# FM375_LQFP64_SOCKET.net
KiCad netlist of a schematic drawn in Altium Designer
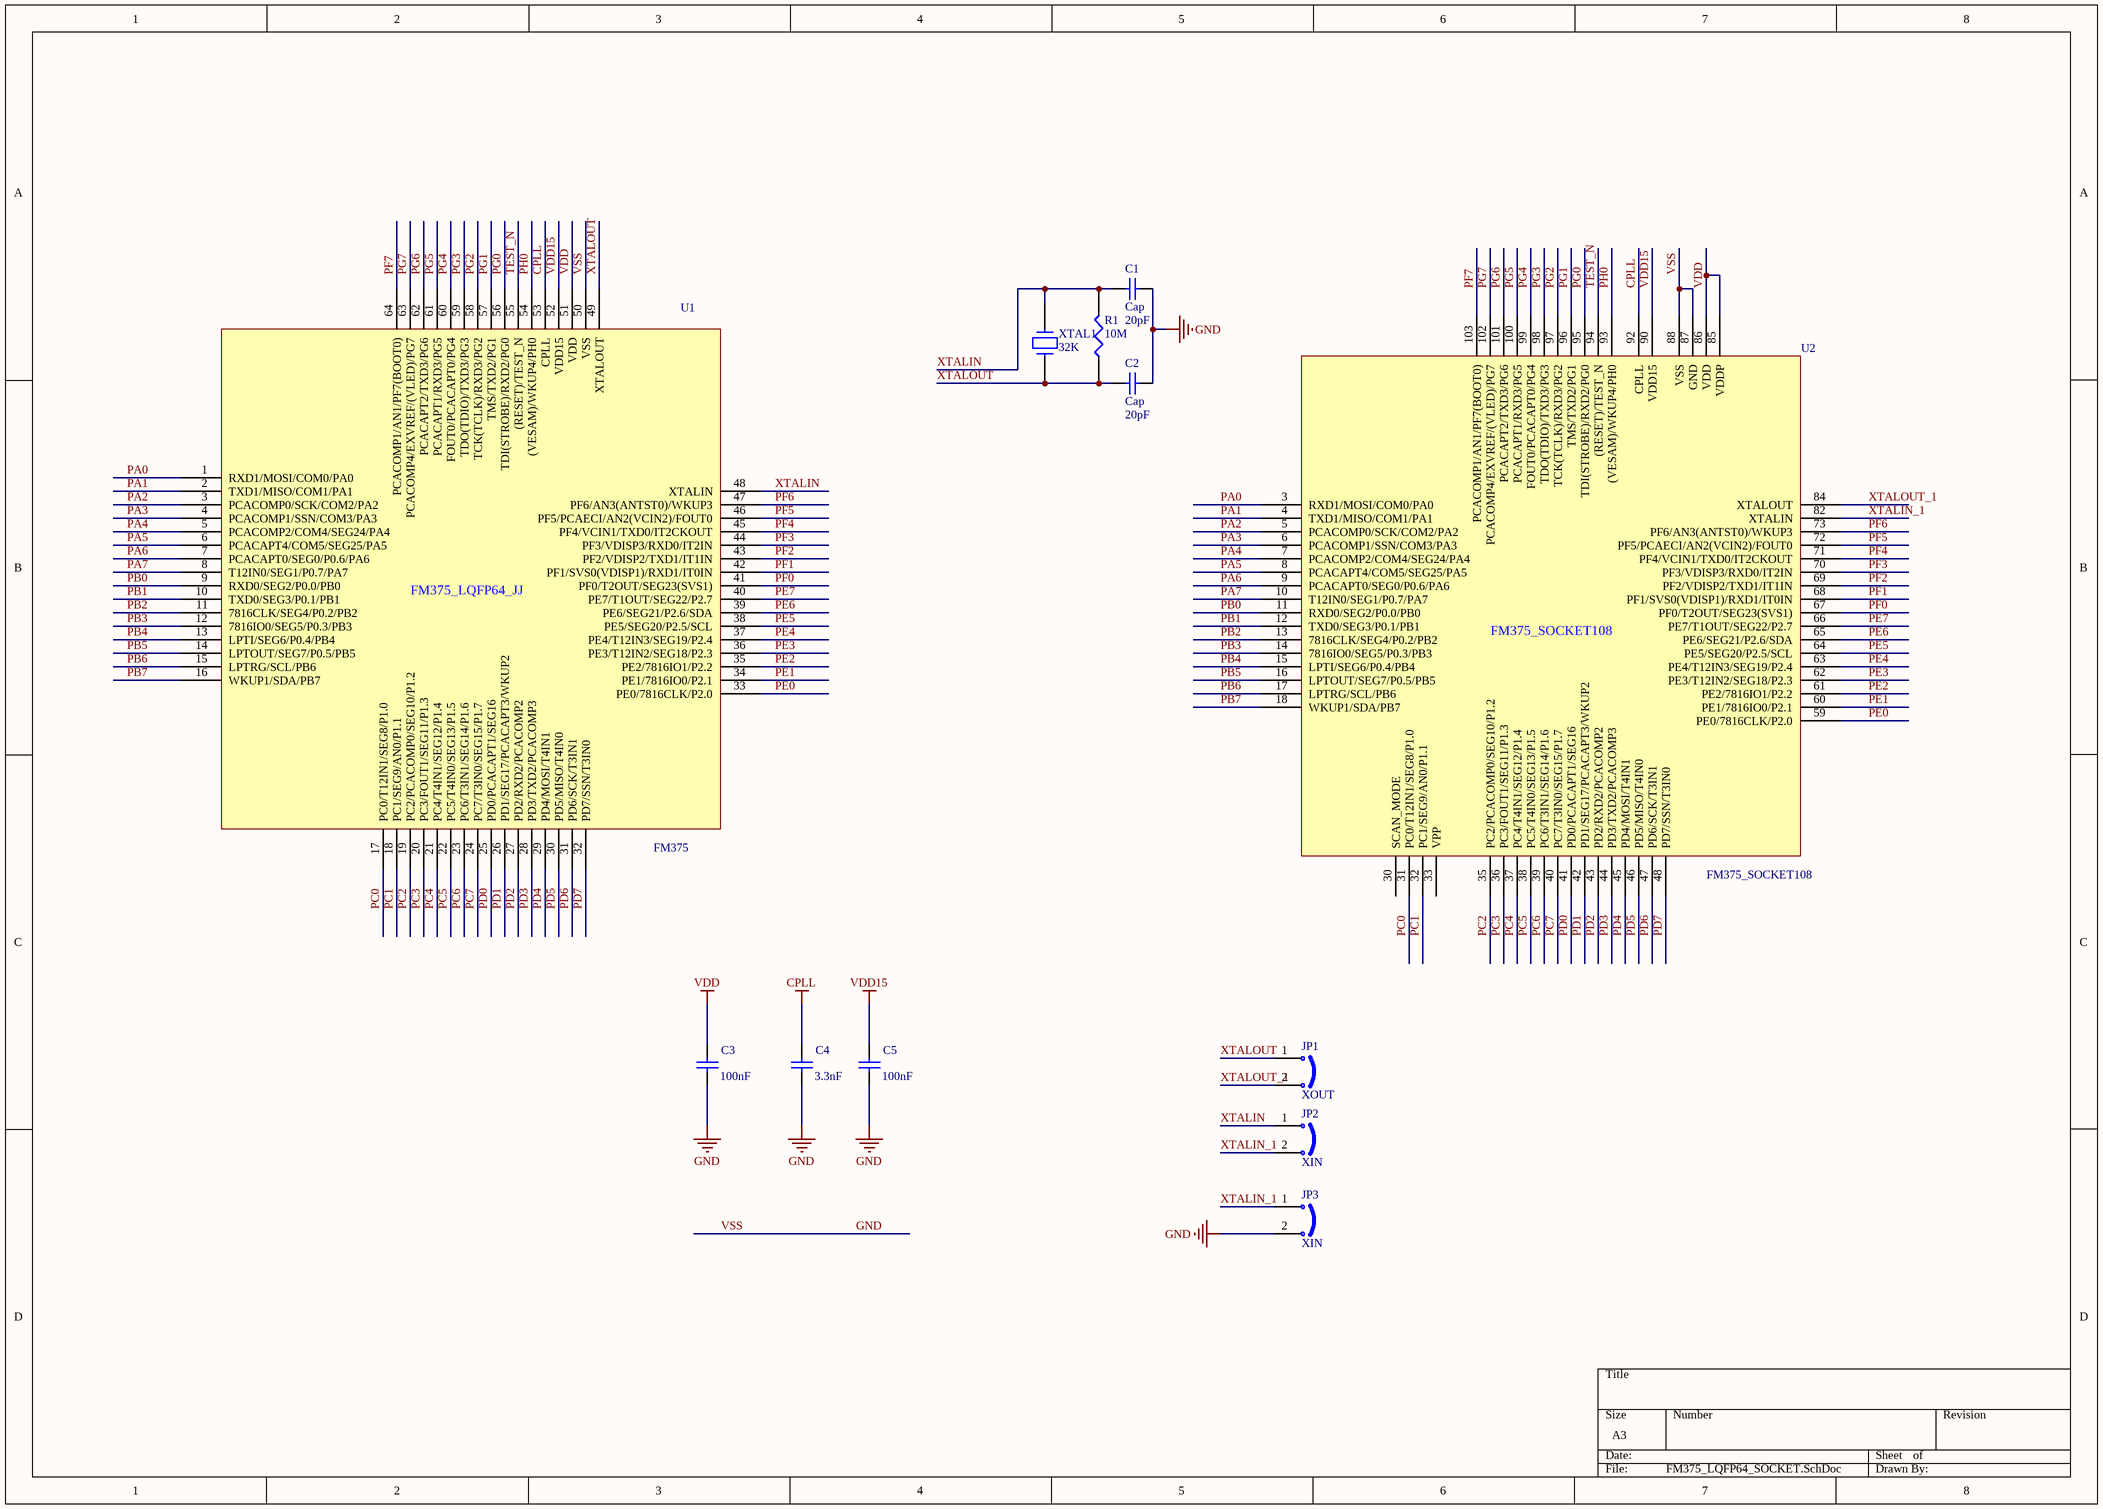
[diagram p0: FM375_LQFP64_SOCKET.SchDoc]

(export (version "E")
  (design (tool "Eeschema 10.0.6"))
  (components
    (comp (ref "C1")
      (value "Cap")
      (footprint "0805")
      (description "Capacitor")
      (fields (field (name "ALTIUM_VALUE") "20pF") (field (name "PUBLISHER") "Altium Limited"))
      (libsource (lib "Miscellaneous Devices") (part "Cap"))
    )
    (comp (ref "C2")
      (value "Cap")
      (footprint "0805")
      (description "Capacitor")
      (fields (field (name "ALTIUM_VALUE") "20pF") (field (name "PUBLISHER") "Altium Limited"))
      (libsource (lib "Miscellaneous Devices") (part "Cap"))
    )
    (comp (ref "C3")
      (value "100nF")
      (footprint "0805")
      (description "Capacitor")
      (fields (field (name "PUBLISHER") "Altium Limited"))
      (libsource (lib "Miscellaneous Devices") (part "Cap"))
    )
    (comp (ref "C4")
      (value "3.3nF")
      (footprint "0805")
      (description "Capacitor")
      (fields (field (name "PUBLISHER") "Altium Limited"))
      (libsource (lib "Miscellaneous Devices") (part "Cap"))
    )
    (comp (ref "C5")
      (value "100nF")
      (footprint "0805")
      (description "Capacitor")
      (fields (field (name "PUBLISHER") "Altium Limited"))
      (libsource (lib "Miscellaneous Devices") (part "Cap"))
    )
    (comp (ref "JP1")
      (value "XOUT")
      (footprint "0603_SHORT")
      (description "Jumper")
      (libsource (lib "FM301_TEST") (part "JUMPER"))
    )
    (comp (ref "JP2")
      (value "XIN")
      (footprint "0603_SHORT")
      (description "Jumper")
      (libsource (lib "FM301_TEST") (part "JUMPER"))
    )
    (comp (ref "JP3")
      (value "XIN")
      (footprint "FM318_SOCKET:0603_SHORT")
      (description "Jumper")
      (libsource (lib "FM301_TEST") (part "JUMPER"))
    )
    (comp (ref "R1") (value "10M") (footprint "0805") (libsource (lib "FM301_TEST") (part "RES1")))
    (comp (ref "U1")
      (value "FM375")
      (footprint "QFP64_10*10_JJ")
      (libsource (lib "FM375_LQFP64_SOCKET") (part "LQFP64-JJ"))
    )
    (comp (ref "U2")
      (value "FM375_SOCKET108")
      (footprint "SOCKET108_LARGE")
      (libsource (lib "FM375_SOCKET") (part "FM375_SOCKET108"))
    )
    (comp (ref "XTAL1")
      (value "32K")
      (footprint "XTAL-RB32K_2")
      (description "Crystal")
      (libsource (lib "FM301_TEST") (part "CRYSTAL"))
    )
  )
  (nets
    (net (code "1") (name "/PA0") (class "Default")
      (node (ref "U1") (pin "1") (pinfunction "RXD1/MOSI/COM0/PA0_1") (pintype "passive"))
      (node (ref "U2") (pin "3") (pinfunction "RXD1/MOSI/COM0/PA0_3") (pintype "passive"))
    )
    (net (code "2") (name "/PA1") (class "Default")
      (node (ref "U1") (pin "2") (pinfunction "TXD1/MISO/COM1/PA1_2") (pintype "passive"))
      (node (ref "U2") (pin "4") (pinfunction "TXD1/MISO/COM1/PA1_4") (pintype "passive"))
    )
    (net (code "3") (name "/PA2") (class "Default")
      (node (ref "U1") (pin "3") (pinfunction "PCACOMP0/SCK/COM2/PA2_3") (pintype "passive"))
      (node (ref "U2") (pin "5") (pinfunction "PCACOMP0/SCK/COM2/PA2_5") (pintype "passive"))
    )
    (net (code "4") (name "/PA3") (class "Default")
      (node (ref "U1") (pin "4") (pinfunction "PCACOMP1/SSN/COM3/PA3_4") (pintype "passive"))
      (node (ref "U2") (pin "6") (pinfunction "PCACOMP1/SSN/COM3/PA3_6") (pintype "passive"))
    )
    (net (code "5") (name "/PA4") (class "Default")
      (node (ref "U1") (pin "5") (pinfunction "PCACOMP2/COM4/SEG24/PA4_5") (pintype "passive"))
      (node (ref "U2") (pin "7") (pinfunction "PCACOMP2/COM4/SEG24/PA4_7") (pintype "passive"))
    )
    (net (code "6") (name "/PA5") (class "Default")
      (node (ref "U1") (pin "6") (pinfunction "PCACAPT4/COM5/SEG25/PA5_6") (pintype "passive"))
      (node (ref "U2") (pin "8") (pinfunction "PCACAPT4/COM5/SEG25/PA5_8") (pintype "passive"))
    )
    (net (code "7") (name "/PA6") (class "Default")
      (node (ref "U1") (pin "7") (pinfunction "PCACAPT0/SEG0/P0.6/PA6_7") (pintype "passive"))
      (node (ref "U2") (pin "9") (pinfunction "PCACAPT0/SEG0/P0.6/PA6_9") (pintype "passive"))
    )
    (net (code "8") (name "/PA7") (class "Default")
      (node (ref "U1") (pin "8") (pinfunction "T12IN0/SEG1/P0.7/PA7_8") (pintype "passive"))
      (node (ref "U2") (pin "10") (pinfunction "T12IN0/SEG1/P0.7/PA7_10") (pintype "passive"))
    )
    (net (code "9") (name "/PB0") (class "Default")
      (node (ref "U1") (pin "9") (pinfunction "RXD0/SEG2/P0.0/PB0_9") (pintype "passive"))
      (node (ref "U2") (pin "11") (pinfunction "RXD0/SEG2/P0.0/PB0_11") (pintype "passive"))
    )
    (net (code "10") (name "/PB1") (class "Default")
      (node (ref "U1") (pin "10") (pinfunction "TXD0/SEG3/P0.1/PB1_10") (pintype "passive"))
      (node (ref "U2") (pin "12") (pinfunction "TXD0/SEG3/P0.1/PB1_12") (pintype "passive"))
    )
    (net (code "11") (name "/PB2") (class "Default")
      (node (ref "U1") (pin "11") (pinfunction "7816CLK/SEG4/P0.2/PB2_11") (pintype "passive"))
      (node (ref "U2") (pin "13") (pinfunction "7816CLK/SEG4/P0.2/PB2_13") (pintype "passive"))
    )
    (net (code "12") (name "/PB3") (class "Default")
      (node (ref "U1") (pin "12") (pinfunction "7816IO0/SEG5/P0.3/PB3_12") (pintype "passive"))
      (node (ref "U2") (pin "14") (pinfunction "7816IO0/SEG5/P0.3/PB3_14") (pintype "passive"))
    )
    (net (code "13") (name "/PB4") (class "Default")
      (node (ref "U1") (pin "13") (pinfunction "LPTI/SEG6/P0.4/PB4_13") (pintype "passive"))
      (node (ref "U2") (pin "15") (pinfunction "LPTI/SEG6/P0.4/PB4_15") (pintype "passive"))
    )
    (net (code "14") (name "/PB5") (class "Default")
      (node (ref "U1") (pin "14") (pinfunction "LPTOUT/SEG7/P0.5/PB5_14") (pintype "passive"))
      (node (ref "U2") (pin "16") (pinfunction "LPTOUT/SEG7/P0.5/PB5_16") (pintype "passive"))
    )
    (net (code "15") (name "/PB6") (class "Default")
      (node (ref "U1") (pin "15") (pinfunction "LPTRG/SCL/PB6_15") (pintype "passive"))
      (node (ref "U2") (pin "17") (pinfunction "LPTRG/SCL/PB6_17") (pintype "passive"))
    )
    (net (code "16") (name "/PB7") (class "Default")
      (node (ref "U1") (pin "16") (pinfunction "WKUP1/SDA/PB7_16") (pintype "passive"))
      (node (ref "U2") (pin "18") (pinfunction "WKUP1/SDA/PB7_18") (pintype "passive"))
    )
    (net (code "17") (name "/PC0") (class "Default")
      (node (ref "U1") (pin "17") (pinfunction "PC0/T12IN1/SEG8/P1.0_17") (pintype "passive"))
      (node (ref "U2") (pin "31") (pinfunction "PC0/T12IN1/SEG8/P1.0_31") (pintype "passive"))
    )
    (net (code "18") (name "/PC1") (class "Default")
      (node (ref "U1") (pin "18") (pinfunction "PC1/SEG9/AN0/P1.1_18") (pintype "passive"))
      (node (ref "U2") (pin "32") (pinfunction "PC1/SEG9/AN0/P1.1_32") (pintype "passive"))
    )
    (net (code "19") (name "/PC2") (class "Default")
      (node (ref "U1") (pin "19") (pinfunction "PC2/PCACOMP0/SEG10/P1.2_19") (pintype "passive"))
      (node (ref "U2") (pin "35") (pinfunction "PC2/PCACOMP0/SEG10/P1.2_35") (pintype "passive"))
    )
    (net (code "20") (name "/PC3") (class "Default")
      (node (ref "U1") (pin "20") (pinfunction "PC3/FOUT1/SEG11/P1.3_20") (pintype "passive"))
      (node (ref "U2") (pin "36") (pinfunction "PC3/FOUT1/SEG11/P1.3_36") (pintype "passive"))
    )
    (net (code "21") (name "/PC4") (class "Default")
      (node (ref "U1") (pin "21") (pinfunction "PC4/T4IN1/SEG12/P1.4_21") (pintype "passive"))
      (node (ref "U2") (pin "37") (pinfunction "PC4/T4IN1/SEG12/P1.4_37") (pintype "passive"))
    )
    (net (code "22") (name "/PC5") (class "Default")
      (node (ref "U1") (pin "22") (pinfunction "PC5/T4IN0/SEG13/P1.5_22") (pintype "passive"))
      (node (ref "U2") (pin "38") (pinfunction "PC5/T4IN0/SEG13/P1.5_38") (pintype "passive"))
    )
    (net (code "23") (name "/PC6") (class "Default")
      (node (ref "U1") (pin "23") (pinfunction "PC6/T3IN1/SEG14/P1.6_23") (pintype "passive"))
      (node (ref "U2") (pin "39") (pinfunction "PC6/T3IN1/SEG14/P1.6_39") (pintype "passive"))
    )
    (net (code "24") (name "/PC7") (class "Default")
      (node (ref "U1") (pin "24") (pinfunction "PC7/T3IN0/SEG15/P1.7_24") (pintype "passive"))
      (node (ref "U2") (pin "40") (pinfunction "PC7/T3IN0/SEG15/P1.7_40") (pintype "passive"))
    )
    (net (code "25") (name "/PD0") (class "Default")
      (node (ref "U1") (pin "25") (pinfunction "PD0/PCACAPT1/SEG16_25") (pintype "passive"))
      (node (ref "U2") (pin "41") (pinfunction "PD0/PCACAPT1/SEG16_41") (pintype "passive"))
    )
    (net (code "26") (name "/PD1") (class "Default")
      (node (ref "U1") (pin "26") (pinfunction "PD1/SEG17/PCACAPT3/WKUP2_26") (pintype "passive"))
      (node (ref "U2") (pin "42") (pinfunction "PD1/SEG17/PCACAPT3/WKUP2_42") (pintype "passive"))
    )
    (net (code "27") (name "/PD2") (class "Default")
      (node (ref "U1") (pin "27") (pinfunction "PD2/RXD2/PCACOMP2_27") (pintype "passive"))
      (node (ref "U2") (pin "43") (pinfunction "PD2/RXD2/PCACOMP2_43") (pintype "passive"))
    )
    (net (code "28") (name "/PD3") (class "Default")
      (node (ref "U1") (pin "28") (pinfunction "PD3/TXD2/PCACOMP3_28") (pintype "passive"))
      (node (ref "U2") (pin "44") (pinfunction "PD3/TXD2/PCACOMP3_44") (pintype "passive"))
    )
    (net (code "29") (name "/PD4") (class "Default")
      (node (ref "U1") (pin "29") (pinfunction "PD4/MOSI/T4IN1_29") (pintype "passive"))
      (node (ref "U2") (pin "45") (pinfunction "PD4/MOSI/T4IN1_45") (pintype "passive"))
    )
    (net (code "30") (name "/PD5") (class "Default")
      (node (ref "U1") (pin "30") (pinfunction "PD5/MISO/T4IN0_30") (pintype "passive"))
      (node (ref "U2") (pin "46") (pinfunction "PD5/MISO/T4IN0_46") (pintype "passive"))
    )
    (net (code "31") (name "/PD6") (class "Default")
      (node (ref "U1") (pin "31") (pinfunction "PD6/SCK/T3IN1_31") (pintype "passive"))
      (node (ref "U2") (pin "47") (pinfunction "PD6/SCK/T3IN1_47") (pintype "passive"))
    )
    (net (code "32") (name "/PD7") (class "Default")
      (node (ref "U1") (pin "32") (pinfunction "PD7/SSN/T3IN0_32") (pintype "passive"))
      (node (ref "U2") (pin "48") (pinfunction "PD7/SSN/T3IN0_48") (pintype "passive"))
    )
    (net (code "33") (name "/PE0") (class "Default")
      (node (ref "U1") (pin "33") (pinfunction "PE0/7816CLK/P2.0_33") (pintype "passive"))
      (node (ref "U2") (pin "59") (pinfunction "PE0/7816CLK/P2.0_59") (pintype "passive"))
    )
    (net (code "34") (name "/PE1") (class "Default")
      (node (ref "U1") (pin "34") (pinfunction "PE1/7816IO0/P2.1_34") (pintype "passive"))
      (node (ref "U2") (pin "60") (pinfunction "PE1/7816IO0/P2.1_60") (pintype "passive"))
    )
    (net (code "35") (name "/PE2") (class "Default")
      (node (ref "U1") (pin "35") (pinfunction "PE2/7816IO1/P2.2_35") (pintype "passive"))
      (node (ref "U2") (pin "61") (pinfunction "PE2/7816IO1/P2.2_61") (pintype "passive"))
    )
    (net (code "36") (name "/PE3") (class "Default")
      (node (ref "U1") (pin "36") (pinfunction "PE3/T12IN2/SEG18/P2.3_36") (pintype "passive"))
      (node (ref "U2") (pin "62") (pinfunction "PE3/T12IN2/SEG18/P2.3_62") (pintype "passive"))
    )
    (net (code "37") (name "/PE4") (class "Default")
      (node (ref "U1") (pin "37") (pinfunction "PE4/T12IN3/SEG19/P2.4_37") (pintype "passive"))
      (node (ref "U2") (pin "63") (pinfunction "PE4/T12IN3/SEG19/P2.4_63") (pintype "passive"))
    )
    (net (code "38") (name "/PE5") (class "Default")
      (node (ref "U1") (pin "38") (pinfunction "PE5/SEG20/P2.5/SCL_38") (pintype "passive"))
      (node (ref "U2") (pin "64") (pinfunction "PE5/SEG20/P2.5/SCL_64") (pintype "passive"))
    )
    (net (code "39") (name "/PE6") (class "Default")
      (node (ref "U1") (pin "39") (pinfunction "PE6/SEG21/P2.6/SDA_39") (pintype "passive"))
      (node (ref "U2") (pin "65") (pinfunction "PE6/SEG21/P2.6/SDA_65") (pintype "passive"))
    )
    (net (code "40") (name "/PE7") (class "Default")
      (node (ref "U1") (pin "40") (pinfunction "PE7/T1OUT/SEG22/P2.7_40") (pintype "passive"))
      (node (ref "U2") (pin "66") (pinfunction "PE7/T1OUT/SEG22/P2.7_66") (pintype "passive"))
    )
    (net (code "41") (name "/PF0") (class "Default")
      (node (ref "U1") (pin "41") (pinfunction "PF0/T2OUT/SEG23(SVS1)_41") (pintype "passive"))
      (node (ref "U2") (pin "67") (pinfunction "PF0/T2OUT/SEG23(SVS1)_67") (pintype "passive"))
    )
    (net (code "42") (name "/PF1") (class "Default")
      (node (ref "U1") (pin "42") (pinfunction "PF1/SVS0(VDISP1)/RXD1/IT0IN_42") (pintype "passive"))
      (node (ref "U2") (pin "68") (pinfunction "PF1/SVS0(VDISP1)/RXD1/IT0IN_68") (pintype "passive"))
    )
    (net (code "43") (name "/PF2") (class "Default")
      (node (ref "U1") (pin "43") (pinfunction "PF2/VDISP2/TXD1/IT1IN_43") (pintype "passive"))
      (node (ref "U2") (pin "69") (pinfunction "PF2/VDISP2/TXD1/IT1IN_69") (pintype "passive"))
    )
    (net (code "44") (name "/PF3") (class "Default")
      (node (ref "U1") (pin "44") (pinfunction "PF3/VDISP3/RXD0/IT2IN_44") (pintype "passive"))
      (node (ref "U2") (pin "70") (pinfunction "PF3/VDISP3/RXD0/IT2IN_70") (pintype "passive"))
    )
    (net (code "45") (name "/PF4") (class "Default")
      (node (ref "U1") (pin "45") (pinfunction "PF4/VCIN1/TXD0/IT2CKOUT_45") (pintype "passive"))
      (node (ref "U2") (pin "71") (pinfunction "PF4/VCIN1/TXD0/IT2CKOUT_71") (pintype "passive"))
    )
    (net (code "46") (name "/PF5") (class "Default")
      (node (ref "U1") (pin "46") (pinfunction "PF5/PCAECI/AN2(VCIN2)/FOUT0_46") (pintype "passive"))
      (node (ref "U2") (pin "72") (pinfunction "PF5/PCAECI/AN2(VCIN2)/FOUT0_72") (pintype "passive"))
    )
    (net (code "47") (name "/PF6") (class "Default")
      (node (ref "U1") (pin "47") (pinfunction "PF6/AN3(ANTST0)/WKUP3_47") (pintype "passive"))
      (node (ref "U2") (pin "73") (pinfunction "PF6/AN3(ANTST0)/WKUP3_73") (pintype "passive"))
    )
    (net (code "48") (name "/PF7") (class "Default")
      (node (ref "U1") (pin "64") (pinfunction "PCACOMP1/AN1/PF7(BOOT0)_64") (pintype "passive"))
      (node (ref "U2") (pin "103") (pinfunction "PCACOMP1/AN1/PF7(BOOT0)_103") (pintype "passive"))
    )
    (net (code "49") (name "/PG0") (class "Default")
      (node (ref "U1") (pin "56") (pinfunction "TDI(STROBE)/RXD2/PG0_56") (pintype "passive"))
      (node (ref "U2") (pin "95") (pinfunction "TDI(STROBE)/RXD2/PG0_95") (pintype "passive"))
    )
    (net (code "50") (name "/PG1") (class "Default")
      (node (ref "U1") (pin "57") (pinfunction "TMS/TXD2/PG1_57") (pintype "passive"))
      (node (ref "U2") (pin "96") (pinfunction "TMS/TXD2/PG1_96") (pintype "passive"))
    )
    (net (code "51") (name "/PG2") (class "Default")
      (node (ref "U1") (pin "58") (pinfunction "TCK(TCLK)/RXD3/PG2_58") (pintype "passive"))
      (node (ref "U2") (pin "97") (pinfunction "TCK(TCLK)/RXD3/PG2_97") (pintype "passive"))
    )
    (net (code "52") (name "/PG3") (class "Default")
      (node (ref "U1") (pin "59") (pinfunction "TDO(TDIO)/TXD3/PG3_59") (pintype "passive"))
      (node (ref "U2") (pin "98") (pinfunction "TDO(TDIO)/TXD3/PG3_98") (pintype "passive"))
    )
    (net (code "53") (name "/PG4") (class "Default")
      (node (ref "U1") (pin "60") (pinfunction "FOUT0/PCACAPT0/PG4_60") (pintype "passive"))
      (node (ref "U2") (pin "99") (pinfunction "FOUT0/PCACAPT0/PG4_99") (pintype "passive"))
    )
    (net (code "54") (name "/PG5") (class "Default")
      (node (ref "U1") (pin "61") (pinfunction "PCACAPT1/RXD3/PG5_61") (pintype "passive"))
      (node (ref "U2") (pin "100") (pinfunction "PCACAPT1/RXD3/PG5_100") (pintype "passive"))
    )
    (net (code "55") (name "/PG6") (class "Default")
      (node (ref "U1") (pin "62") (pinfunction "PCACAPT2/TXD3/PG6_62") (pintype "passive"))
      (node (ref "U2") (pin "101") (pinfunction "PCACAPT2/TXD3/PG6_101") (pintype "passive"))
    )
    (net (code "56") (name "/PG7") (class "Default")
      (node (ref "U1") (pin "63") (pinfunction "PCACOMP4/EXVREF/(VLED)/PG7_63") (pintype "passive"))
      (node (ref "U2") (pin "102") (pinfunction "PCACOMP4/EXVREF/(VLED)/PG7_102") (pintype "passive"))
    )
    (net (code "57") (name "/PH0") (class "Default")
      (node (ref "U1") (pin "54") (pinfunction "(VESAM)/WKUP4/PH0_54") (pintype "passive"))
      (node (ref "U2") (pin "93") (pinfunction "(VESAM)/WKUP4/PH0_93") (pintype "passive"))
    )
    (net (code "58") (name "/TEST_N") (class "Default")
      (node (ref "U1") (pin "55") (pinfunction "(RESET)/TEST_N_55") (pintype "passive"))
      (node (ref "U2") (pin "94") (pinfunction "(RESET)/TEST_N_94") (pintype "passive"))
    )
    (net (code "59") (name "/XTALIN") (class "Default")
      (node (ref "C1") (pin "1") (pinfunction "1_1") (pintype "passive"))
      (node (ref "JP2") (pin "1") (pinfunction "1_1") (pintype "passive"))
      (node (ref "R1") (pin "2") (pinfunction "2_2") (pintype "passive"))
      (node (ref "U1") (pin "48") (pinfunction "XTALIN_48") (pintype "passive"))
      (node (ref "XTAL1") (pin "1") (pinfunction "1_1") (pintype "passive"))
    )
    (net (code "60") (name "/XTALIN_1") (class "Default")
      (node (ref "JP2") (pin "2") (pinfunction "2_2") (pintype "passive"))
      (node (ref "JP3") (pin "1") (pinfunction "1_1") (pintype "passive"))
      (node (ref "U2") (pin "82") (pinfunction "XTALIN_82") (pintype "passive"))
    )
    (net (code "61") (name "/XTALOUT") (class "Default")
      (node (ref "C2") (pin "1") (pinfunction "1_1") (pintype "passive"))
      (node (ref "JP1") (pin "1") (pinfunction "1_1") (pintype "passive"))
      (node (ref "R1") (pin "1") (pinfunction "1_1") (pintype "passive"))
      (node (ref "U1") (pin "49") (pinfunction "XTALOUT_49") (pintype "passive"))
      (node (ref "XTAL1") (pin "2") (pinfunction "2_2") (pintype "passive"))
    )
    (net (code "62") (name "/XTALOUT_1") (class "Default")
      (node (ref "JP1") (pin "2") (pinfunction "2_2") (pintype "passive"))
      (node (ref "U2") (pin "84") (pinfunction "XTALOUT_84") (pintype "passive"))
    )
    (net (code "63") (name "CPLL") (class "Default")
      (node (ref "C4") (pin "2") (pinfunction "2_2") (pintype "passive"))
      (node (ref "U1") (pin "53") (pinfunction "CPLL_53") (pintype "passive"))
      (node (ref "U2") (pin "92") (pinfunction "CPLL_92") (pintype "passive"))
    )
    (net (code "64") (name "GND") (class "Default")
      (node (ref "C1") (pin "2") (pinfunction "2_2") (pintype "passive"))
      (node (ref "C2") (pin "2") (pinfunction "2_2") (pintype "passive"))
      (node (ref "C3") (pin "1") (pinfunction "1_1") (pintype "passive"))
      (node (ref "C4") (pin "1") (pinfunction "1_1") (pintype "passive"))
      (node (ref "C5") (pin "1") (pinfunction "1_1") (pintype "passive"))
      (node (ref "JP3") (pin "2") (pinfunction "2_2") (pintype "passive"))
      (node (ref "U1") (pin "50") (pinfunction "VSS_50") (pintype "passive"))
      (node (ref "U2") (pin "87") (pinfunction "GND_87") (pintype "passive"))
      (node (ref "U2") (pin "88") (pinfunction "VSS_88") (pintype "passive"))
    )
    (net (code "65") (name "VDD") (class "Default")
      (node (ref "C3") (pin "2") (pinfunction "2_2") (pintype "passive"))
      (node (ref "U1") (pin "51") (pinfunction "VDD_51") (pintype "passive"))
      (node (ref "U2") (pin "85") (pinfunction "VDDP_85") (pintype "passive"))
      (node (ref "U2") (pin "86") (pinfunction "VDD_86") (pintype "passive"))
    )
    (net (code "66") (name "VDD15") (class "Default")
      (node (ref "C5") (pin "2") (pinfunction "2_2") (pintype "passive"))
      (node (ref "U1") (pin "52") (pinfunction "VDD15_52") (pintype "passive"))
      (node (ref "U2") (pin "90") (pinfunction "VDD15_90") (pintype "passive"))
    )
    (net (code "67") (name "unconnected-(U2-SCAN_MODE-Pad30)") (class "Default")
      (node (ref "U2") (pin "30") (pinfunction "SCAN_MODE_30") (pintype "passive"))
    )
    (net (code "68") (name "unconnected-(U2-VPP-Pad33)") (class "Default")
      (node (ref "U2") (pin "33") (pinfunction "VPP_33") (pintype "passive"))
    )
  )
)
